# STorM32_NT_imu_v10-mpu6000.net
KiCad netlist of a schematic drawn in EAGLE
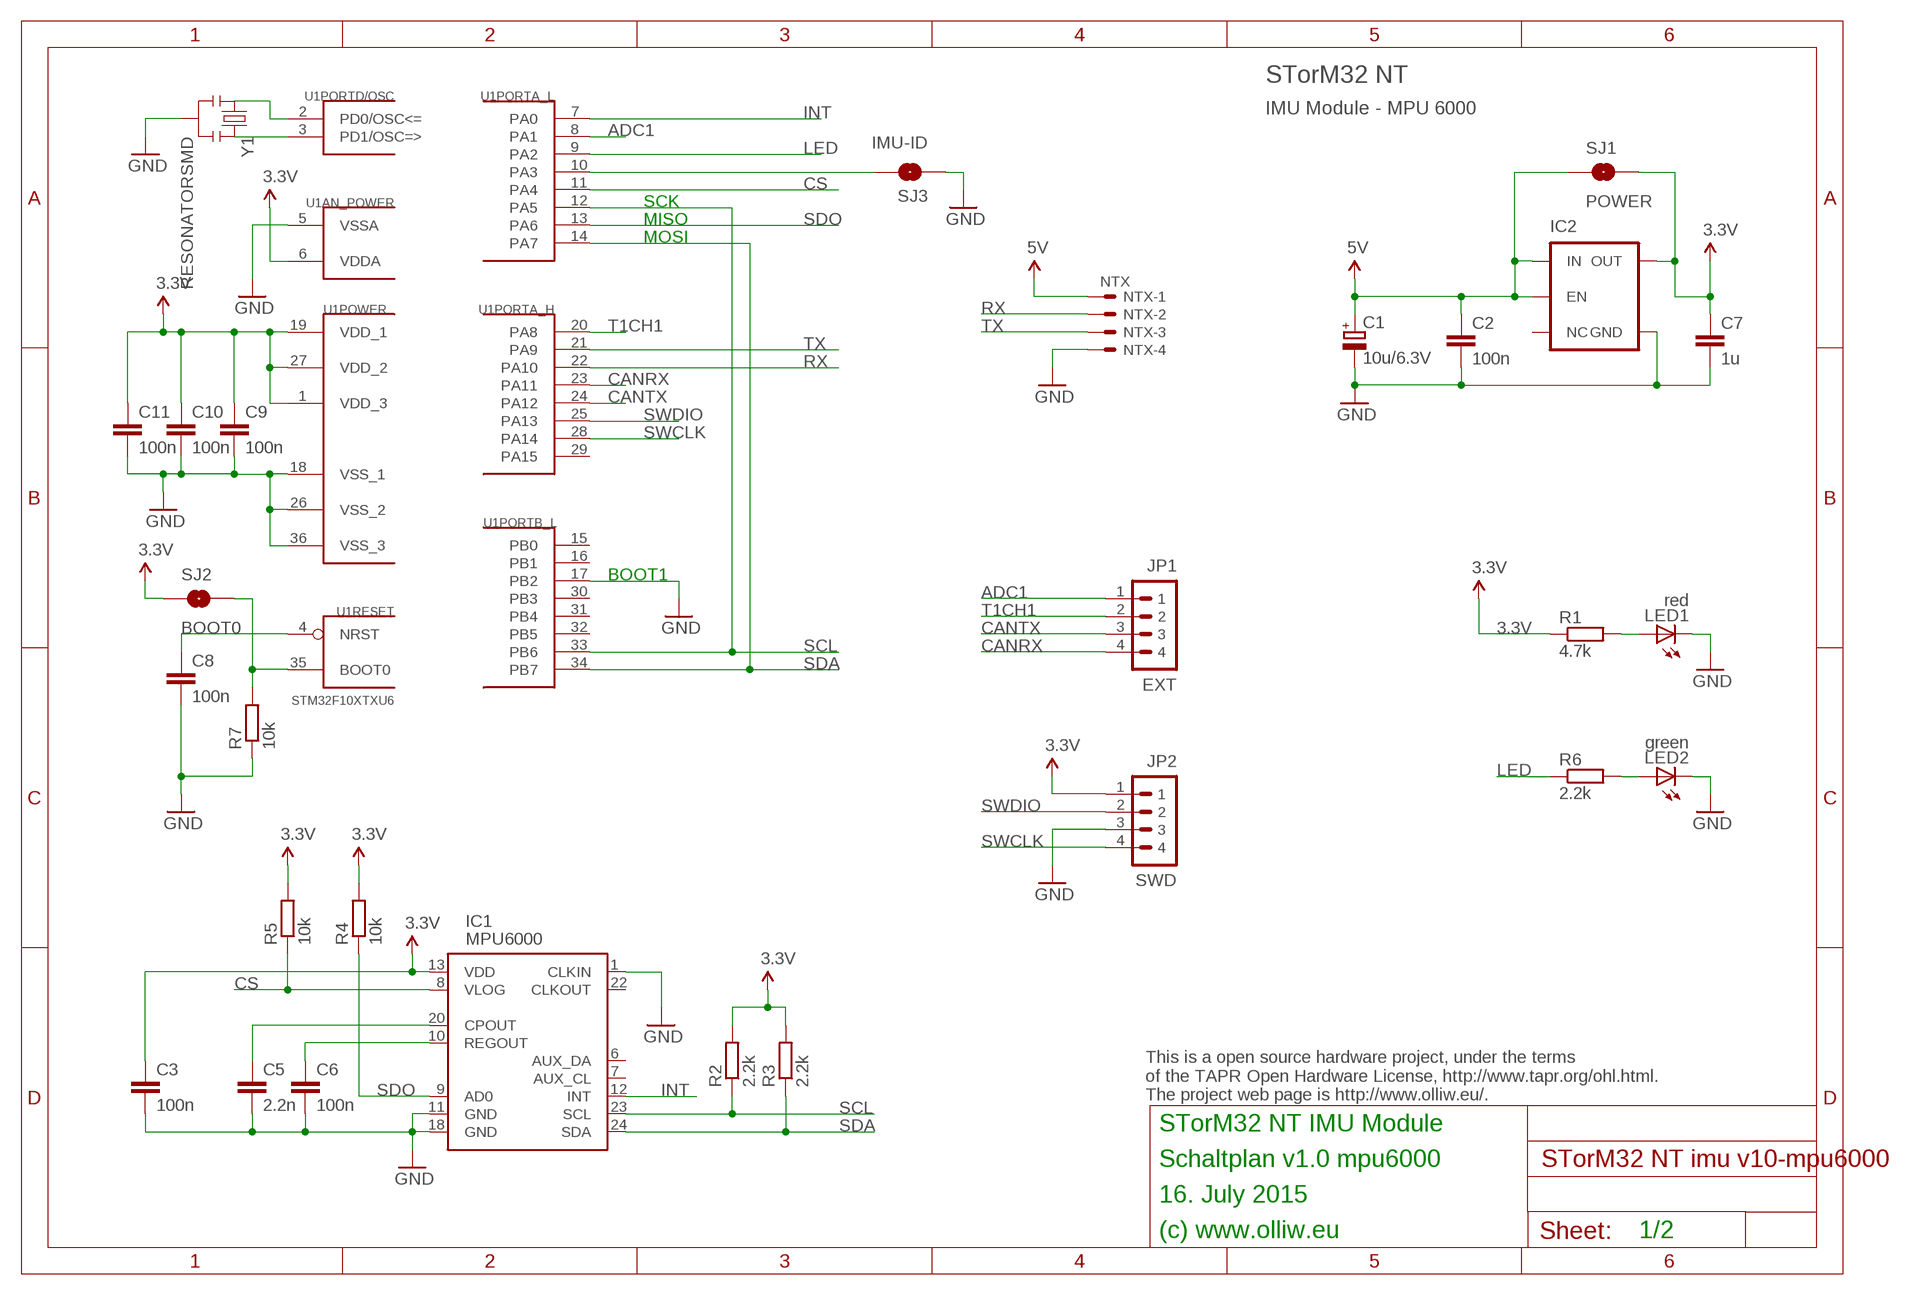
[diagram p0: schematic, sheet 1]

(export (version "E")
  (design (tool "Eeschema 10.0.6"))
  (components
    (comp (ref "C1")
      (value "10u/6.3V")
      (footprint "eagle-import:SMC_B")
      (libsource (lib "eagle-import") (part "CPOL-EUSMCB"))
    )
    (comp (ref "C2")
      (value "100n")
      (footprint "eagle-import:C0603")
      (libsource (lib "eagle-import") (part "C-EUC0603"))
    )
    (comp (ref "C3")
      (value "100n")
      (footprint "eagle-import:C0603")
      (libsource (lib "eagle-import") (part "C-EUC0603"))
    )
    (comp (ref "C5")
      (value "2.2n")
      (footprint "eagle-import:C0603")
      (libsource (lib "eagle-import") (part "C-EUC0603"))
    )
    (comp (ref "C6")
      (value "100n")
      (footprint "eagle-import:C0603")
      (libsource (lib "eagle-import") (part "C-EUC0603"))
    )
    (comp (ref "C7")
      (value "1u")
      (footprint "eagle-import:C0603")
      (libsource (lib "eagle-import") (part "C-EUC0603"))
    )
    (comp (ref "C8")
      (value "100n")
      (footprint "eagle-import:C0402")
      (libsource (lib "eagle-import") (part "C-EUC0402"))
    )
    (comp (ref "C9")
      (value "100n")
      (footprint "eagle-import:C0603")
      (libsource (lib "eagle-import") (part "C-EUC0603"))
    )
    (comp (ref "C10")
      (value "100n")
      (footprint "eagle-import:C0402")
      (libsource (lib "eagle-import") (part "C-EUC0402"))
    )
    (comp (ref "C11")
      (value "100n")
      (footprint "eagle-import:C0603")
      (libsource (lib "eagle-import") (part "C-EUC0603"))
    )
    (comp (ref "IC1")
      (value "MPU6000")
      (footprint "eagle-import:QFN-24")
      (libsource (lib "eagle-import") (part "IMU3000"))
    )
    (comp (ref "IC2")
      (value "V_REG_TPS76433SOT23-5")
      (footprint "eagle-import:SOT23-5")
      (libsource (lib "eagle-import") (part "V_REG_TPS76433SOT23-5"))
    )
    (comp (ref "JP1")
      (value "EXT")
      (footprint "eagle-import:4X1_1P27_OCT_BILEX")
      (libsource (lib "eagle-import") (part "P4X1_1P27-OCT_BILEX"))
    )
    (comp (ref "JP2")
      (value "SWD")
      (footprint "eagle-import:4X1_1P27_OCT_BILEX")
      (libsource (lib "eagle-import") (part "P4X1_1P27-OCT_BILEX"))
    )
    (comp (ref "LED1")
      (value "red")
      (footprint "eagle-import:CHIPLED_0603")
      (libsource (lib "eagle-import") (part "LEDCHIPLED_0603"))
    )
    (comp (ref "LED2")
      (value "green")
      (footprint "eagle-import:CHIPLED_0603")
      (libsource (lib "eagle-import") (part "LEDCHIPLED_0603"))
    )
    (comp (ref "NTX")
      (value "NTX")
      (footprint "eagle-import:SM04B-SRSS-TB")
      (libsource (lib "eagle-import") (part "?M04B-SRSS-TBS"))
    )
    (comp (ref "R1")
      (value "4.7k")
      (footprint "eagle-import:R0603")
      (libsource (lib "eagle-import") (part "R-EU_R0603"))
    )
    (comp (ref "R2")
      (value "2.2k")
      (footprint "eagle-import:R0603")
      (libsource (lib "eagle-import") (part "R-EU_R0603"))
    )
    (comp (ref "R3")
      (value "2.2k")
      (footprint "eagle-import:R0603")
      (libsource (lib "eagle-import") (part "R-EU_R0603"))
    )
    (comp (ref "R4")
      (value "10k")
      (footprint "eagle-import:R0603")
      (libsource (lib "eagle-import") (part "R-EU_R0603"))
    )
    (comp (ref "R5")
      (value "10k")
      (footprint "eagle-import:R0603")
      (libsource (lib "eagle-import") (part "R-EU_R0603"))
    )
    (comp (ref "R6")
      (value "2.2k")
      (footprint "eagle-import:R0603")
      (libsource (lib "eagle-import") (part "R-EU_R0603"))
    )
    (comp (ref "R7")
      (value "10k")
      (footprint "eagle-import:R0603")
      (libsource (lib "eagle-import") (part "R-EU_R0603"))
    )
    (comp (ref "SJ1")
      (value "POWER")
      (footprint "eagle-import:SJ_2S-NO")
      (libsource (lib "eagle-import") (part "SOLDERJUMPERNO"))
    )
    (comp (ref "SJ2")
      (value "BOOT0")
      (footprint "eagle-import:SJ_2S-NO")
      (libsource (lib "eagle-import") (part "SOLDERJUMPERNO"))
    )
    (comp (ref "SJ3")
      (value "IMU-ID")
      (footprint "eagle-import:SJ_2S-NO")
      (libsource (lib "eagle-import") (part "SOLDERJUMPERNO"))
    )
    (comp (ref "U1")
      (value "STM32F10XTXU6")
      (footprint "eagle-import:VFQFPN36")
      (libsource (lib "eagle-import") (part "STM32F10XTXU6"))
    )
    (comp (ref "Y1")
      (value "RESONATORSMD")
      (footprint "eagle-import:RESONATOR-SMD")
      (libsource (lib "eagle-import") (part "RESONATORSMD"))
    )
  )
  (nets
    (net (code "1") (name "/ADC1") (class "Default")
      (node (ref "JP1") (pin "1") (pinfunction "1_1") (pintype "passive"))
      (node (ref "U1") (pin "8") (pinfunction "PA1_8") (pintype "bidirectional"))
    )
    (net (code "2") (name "/CANRX") (class "Default")
      (node (ref "JP1") (pin "4") (pinfunction "4_4") (pintype "passive"))
      (node (ref "U1") (pin "23") (pinfunction "PA11_23") (pintype "bidirectional"))
    )
    (net (code "3") (name "/CANTX") (class "Default")
      (node (ref "JP1") (pin "3") (pinfunction "3_3") (pintype "passive"))
      (node (ref "U1") (pin "24") (pinfunction "PA12_24") (pintype "bidirectional"))
    )
    (net (code "4") (name "/CS") (class "Default")
      (node (ref "IC1") (pin "8") (pinfunction "VLOG_8") (pintype "bidirectional"))
      (node (ref "R5") (pin "1") (pinfunction "1_1") (pintype "passive"))
      (node (ref "U1") (pin "11") (pinfunction "PA4_11") (pintype "bidirectional"))
    )
    (net (code "5") (name "/INT") (class "Default")
      (node (ref "IC1") (pin "12") (pinfunction "INT_12") (pintype "bidirectional"))
      (node (ref "U1") (pin "7") (pinfunction "PA0_7") (pintype "bidirectional"))
    )
    (net (code "6") (name "/LED") (class "Default")
      (node (ref "R6") (pin "1") (pinfunction "1_1") (pintype "passive"))
      (node (ref "U1") (pin "9") (pinfunction "PA2_9") (pintype "bidirectional"))
    )
    (net (code "7") (name "/RX") (class "Default")
      (node (ref "NTX") (pin "2") (pinfunction "S_2") (pintype "passive"))
      (node (ref "U1") (pin "22") (pinfunction "PA10_22") (pintype "bidirectional"))
    )
    (net (code "8") (name "/SCL") (class "Default")
      (node (ref "IC1") (pin "23") (pinfunction "SCL_23") (pintype "bidirectional"))
      (node (ref "R2") (pin "1") (pinfunction "1_1") (pintype "passive"))
      (node (ref "U1") (pin "12") (pinfunction "PA5_12") (pintype "bidirectional"))
      (node (ref "U1") (pin "33") (pinfunction "PB6_33") (pintype "bidirectional"))
    )
    (net (code "9") (name "/SDA") (class "Default")
      (node (ref "IC1") (pin "24") (pinfunction "SDA_24") (pintype "bidirectional"))
      (node (ref "R3") (pin "1") (pinfunction "1_1") (pintype "passive"))
      (node (ref "U1") (pin "14") (pinfunction "PA7_14") (pintype "bidirectional"))
      (node (ref "U1") (pin "34") (pinfunction "PB7_34") (pintype "bidirectional"))
    )
    (net (code "10") (name "/SDO") (class "Default")
      (node (ref "IC1") (pin "9") (pinfunction "AD0_9") (pintype "bidirectional"))
      (node (ref "R4") (pin "1") (pinfunction "1_1") (pintype "passive"))
      (node (ref "U1") (pin "13") (pinfunction "PA6_13") (pintype "bidirectional"))
    )
    (net (code "11") (name "/SWCLK") (class "Default")
      (node (ref "JP2") (pin "4") (pinfunction "4_4") (pintype "passive"))
      (node (ref "U1") (pin "28") (pinfunction "PA14_28") (pintype "bidirectional"))
    )
    (net (code "12") (name "/SWDIO") (class "Default")
      (node (ref "JP2") (pin "2") (pinfunction "2_2") (pintype "passive"))
      (node (ref "U1") (pin "25") (pinfunction "PA13_25") (pintype "bidirectional"))
    )
    (net (code "13") (name "/T1CH1") (class "Default")
      (node (ref "JP1") (pin "2") (pinfunction "2_2") (pintype "passive"))
      (node (ref "U1") (pin "20") (pinfunction "PA8_20") (pintype "bidirectional"))
    )
    (net (code "14") (name "/TX") (class "Default")
      (node (ref "NTX") (pin "3") (pinfunction "S_3") (pintype "passive"))
      (node (ref "U1") (pin "21") (pinfunction "PA9_21") (pintype "bidirectional"))
    )
    (net (code "15") (name "3.3V") (class "Default")
      (node (ref "C10") (pin "1") (pinfunction "1_1") (pintype "passive"))
      (node (ref "C11") (pin "1") (pinfunction "1_1") (pintype "passive"))
      (node (ref "C3") (pin "1") (pinfunction "1_1") (pintype "passive"))
      (node (ref "C7") (pin "1") (pinfunction "1_1") (pintype "passive"))
      (node (ref "C9") (pin "1") (pinfunction "1_1") (pintype "passive"))
      (node (ref "IC1") (pin "13") (pinfunction "VDD_13") (pintype "bidirectional"))
      (node (ref "IC2") (pin "5") (pinfunction "OUT_5") (pintype "passive"))
      (node (ref "JP2") (pin "1") (pinfunction "1_1") (pintype "passive"))
      (node (ref "R1") (pin "1") (pinfunction "1_1") (pintype "passive"))
      (node (ref "R2") (pin "2") (pinfunction "2_2") (pintype "passive"))
      (node (ref "R3") (pin "2") (pinfunction "2_2") (pintype "passive"))
      (node (ref "R4") (pin "2") (pinfunction "2_2") (pintype "passive"))
      (node (ref "R5") (pin "2") (pinfunction "2_2") (pintype "passive"))
      (node (ref "SJ1") (pin "2") (pinfunction "2_2") (pintype "passive"))
      (node (ref "SJ2") (pin "1") (pinfunction "1_1") (pintype "passive"))
      (node (ref "U1") (pin "1") (pinfunction "VDD_3_1") (pintype "power_in"))
      (node (ref "U1") (pin "19") (pinfunction "VDD_1_19") (pintype "power_in"))
      (node (ref "U1") (pin "27") (pinfunction "VDD_2_27") (pintype "power_in"))
      (node (ref "U1") (pin "6") (pinfunction "VDDA_6") (pintype "power_in"))
    )
    (net (code "16") (name "5V") (class "Default")
      (node (ref "C1") (pin "+") (pinfunction "+_+") (pintype "passive"))
      (node (ref "C2") (pin "1") (pinfunction "1_1") (pintype "passive"))
      (node (ref "IC2") (pin "1") (pinfunction "IN_1") (pintype "input"))
      (node (ref "IC2") (pin "3") (pinfunction "EN_3") (pintype "input"))
      (node (ref "NTX") (pin "1") (pinfunction "S_1") (pintype "passive"))
      (node (ref "SJ1") (pin "1") (pinfunction "1_1") (pintype "passive"))
    )
    (net (code "17") (name "GND") (class "Default")
      (node (ref "C1") (pin "-") (pinfunction "-_-") (pintype "passive"))
      (node (ref "C10") (pin "2") (pinfunction "2_2") (pintype "passive"))
      (node (ref "C11") (pin "2") (pinfunction "2_2") (pintype "passive"))
      (node (ref "C2") (pin "2") (pinfunction "2_2") (pintype "passive"))
      (node (ref "C3") (pin "2") (pinfunction "2_2") (pintype "passive"))
      (node (ref "C5") (pin "2") (pinfunction "2_2") (pintype "passive"))
      (node (ref "C6") (pin "2") (pinfunction "2_2") (pintype "passive"))
      (node (ref "C7") (pin "2") (pinfunction "2_2") (pintype "passive"))
      (node (ref "C8") (pin "2") (pinfunction "2_2") (pintype "passive"))
      (node (ref "C9") (pin "2") (pinfunction "2_2") (pintype "passive"))
      (node (ref "IC1") (pin "1") (pinfunction "CLKIN_1") (pintype "bidirectional"))
      (node (ref "IC1") (pin "11") (pinfunction "GND_11") (pintype "bidirectional"))
      (node (ref "IC1") (pin "18") (pinfunction "GND_18") (pintype "bidirectional"))
      (node (ref "IC2") (pin "2") (pinfunction "GND_2") (pintype "input"))
      (node (ref "JP2") (pin "3") (pinfunction "3_3") (pintype "passive"))
      (node (ref "LED1") (pin "C") (pinfunction "C_C") (pintype "passive"))
      (node (ref "LED2") (pin "C") (pinfunction "C_C") (pintype "passive"))
      (node (ref "NTX") (pin "4") (pinfunction "S_4") (pintype "passive"))
      (node (ref "R7") (pin "1") (pinfunction "1_1") (pintype "passive"))
      (node (ref "SJ3") (pin "1") (pinfunction "1_1") (pintype "passive"))
      (node (ref "U1") (pin "17") (pinfunction "PB2_17") (pintype "bidirectional"))
      (node (ref "U1") (pin "18") (pinfunction "VSS_1_18") (pintype "power_in"))
      (node (ref "U1") (pin "26") (pinfunction "VSS_2_26") (pintype "power_in"))
      (node (ref "U1") (pin "36") (pinfunction "VSS_3_36") (pintype "power_in"))
      (node (ref "U1") (pin "5") (pinfunction "VSSA_5") (pintype "power_in"))
      (node (ref "Y1") (pin "2") (pinfunction "2_2") (pintype "passive"))
    )
    (net (code "18") (name "Net-(IC1-CPOUT)") (class "Default")
      (node (ref "C5") (pin "1") (pinfunction "1_1") (pintype "passive"))
      (node (ref "IC1") (pin "20") (pinfunction "CPOUT_20") (pintype "bidirectional"))
    )
    (net (code "19") (name "Net-(IC1-REGOUT)") (class "Default")
      (node (ref "C6") (pin "1") (pinfunction "1_1") (pintype "passive"))
      (node (ref "IC1") (pin "10") (pinfunction "REGOUT_10") (pintype "bidirectional"))
    )
    (net (code "20") (name "Net-(LED1-PadA)") (class "Default")
      (node (ref "LED1") (pin "A") (pinfunction "A_A") (pintype "passive"))
      (node (ref "R1") (pin "2") (pinfunction "2_2") (pintype "passive"))
    )
    (net (code "21") (name "Net-(LED2-PadA)") (class "Default")
      (node (ref "LED2") (pin "A") (pinfunction "A_A") (pintype "passive"))
      (node (ref "R6") (pin "2") (pinfunction "2_2") (pintype "passive"))
    )
    (net (code "22") (name "Net-(U1C-PA3)") (class "Default")
      (node (ref "SJ3") (pin "2") (pinfunction "2_2") (pintype "passive"))
      (node (ref "U1") (pin "10") (pinfunction "PA3_10") (pintype "bidirectional"))
    )
    (net (code "23") (name "Net-(U1E-PD0{slash}OSC<=)") (class "Default")
      (node (ref "U1") (pin "2") (pinfunction "PD0/OSC<=_2") (pintype "bidirectional"))
      (node (ref "Y1") (pin "1") (pinfunction "1_1") (pintype "passive"))
    )
    (net (code "24") (name "Net-(U1E-PD1{slash}OSC=>)") (class "Default")
      (node (ref "U1") (pin "3") (pinfunction "PD1/OSC=>_3") (pintype "bidirectional"))
      (node (ref "Y1") (pin "3") (pinfunction "3_3") (pintype "passive"))
    )
    (net (code "25") (name "Net-(U1G-BOOT0)") (class "Default")
      (node (ref "R7") (pin "2") (pinfunction "2_2") (pintype "passive"))
      (node (ref "SJ2") (pin "2") (pinfunction "2_2") (pintype "passive"))
      (node (ref "U1") (pin "35") (pinfunction "BOOT0_35") (pintype "input"))
    )
    (net (code "26") (name "Net-(U1G-NRST)") (class "Default")
      (node (ref "C8") (pin "1") (pinfunction "1_1") (pintype "passive"))
      (node (ref "U1") (pin "4") (pinfunction "NRST_4") (pintype "input"))
    )
    (net (code "27") (name "unconnected-(IC1-AUX_CL-Pad7)") (class "Default")
      (node (ref "IC1") (pin "7") (pinfunction "AUX_CL_7") (pintype "bidirectional"))
    )
    (net (code "28") (name "unconnected-(IC1-AUX_DA-Pad6)") (class "Default")
      (node (ref "IC1") (pin "6") (pinfunction "AUX_DA_6") (pintype "bidirectional"))
    )
    (net (code "29") (name "unconnected-(IC1-CLKOUT-Pad22)") (class "Default")
      (node (ref "IC1") (pin "22") (pinfunction "CLKOUT_22") (pintype "bidirectional"))
    )
    (net (code "30") (name "unconnected-(IC2-NC-Pad4)") (class "Default")
      (node (ref "IC2") (pin "4") (pinfunction "NC_4") (pintype "input"))
    )
    (net (code "31") (name "unconnected-(U1B-PA15-Pad29)") (class "Default")
      (node (ref "U1") (pin "29") (pinfunction "PA15_29") (pintype "bidirectional"))
    )
    (net (code "32") (name "unconnected-(U1D-PB0-Pad15)") (class "Default")
      (node (ref "U1") (pin "15") (pinfunction "PB0_15") (pintype "bidirectional"))
    )
    (net (code "33") (name "unconnected-(U1D-PB1-Pad16)") (class "Default")
      (node (ref "U1") (pin "16") (pinfunction "PB1_16") (pintype "bidirectional"))
    )
    (net (code "34") (name "unconnected-(U1D-PB3-Pad30)") (class "Default")
      (node (ref "U1") (pin "30") (pinfunction "PB3_30") (pintype "bidirectional"))
    )
    (net (code "35") (name "unconnected-(U1D-PB4-Pad31)") (class "Default")
      (node (ref "U1") (pin "31") (pinfunction "PB4_31") (pintype "bidirectional"))
    )
    (net (code "36") (name "unconnected-(U1D-PB5-Pad32)") (class "Default")
      (node (ref "U1") (pin "32") (pinfunction "PB5_32") (pintype "bidirectional"))
    )
  )
)
